# LineFollower2.net
KiCad netlist of a schematic drawn in Altium Designer
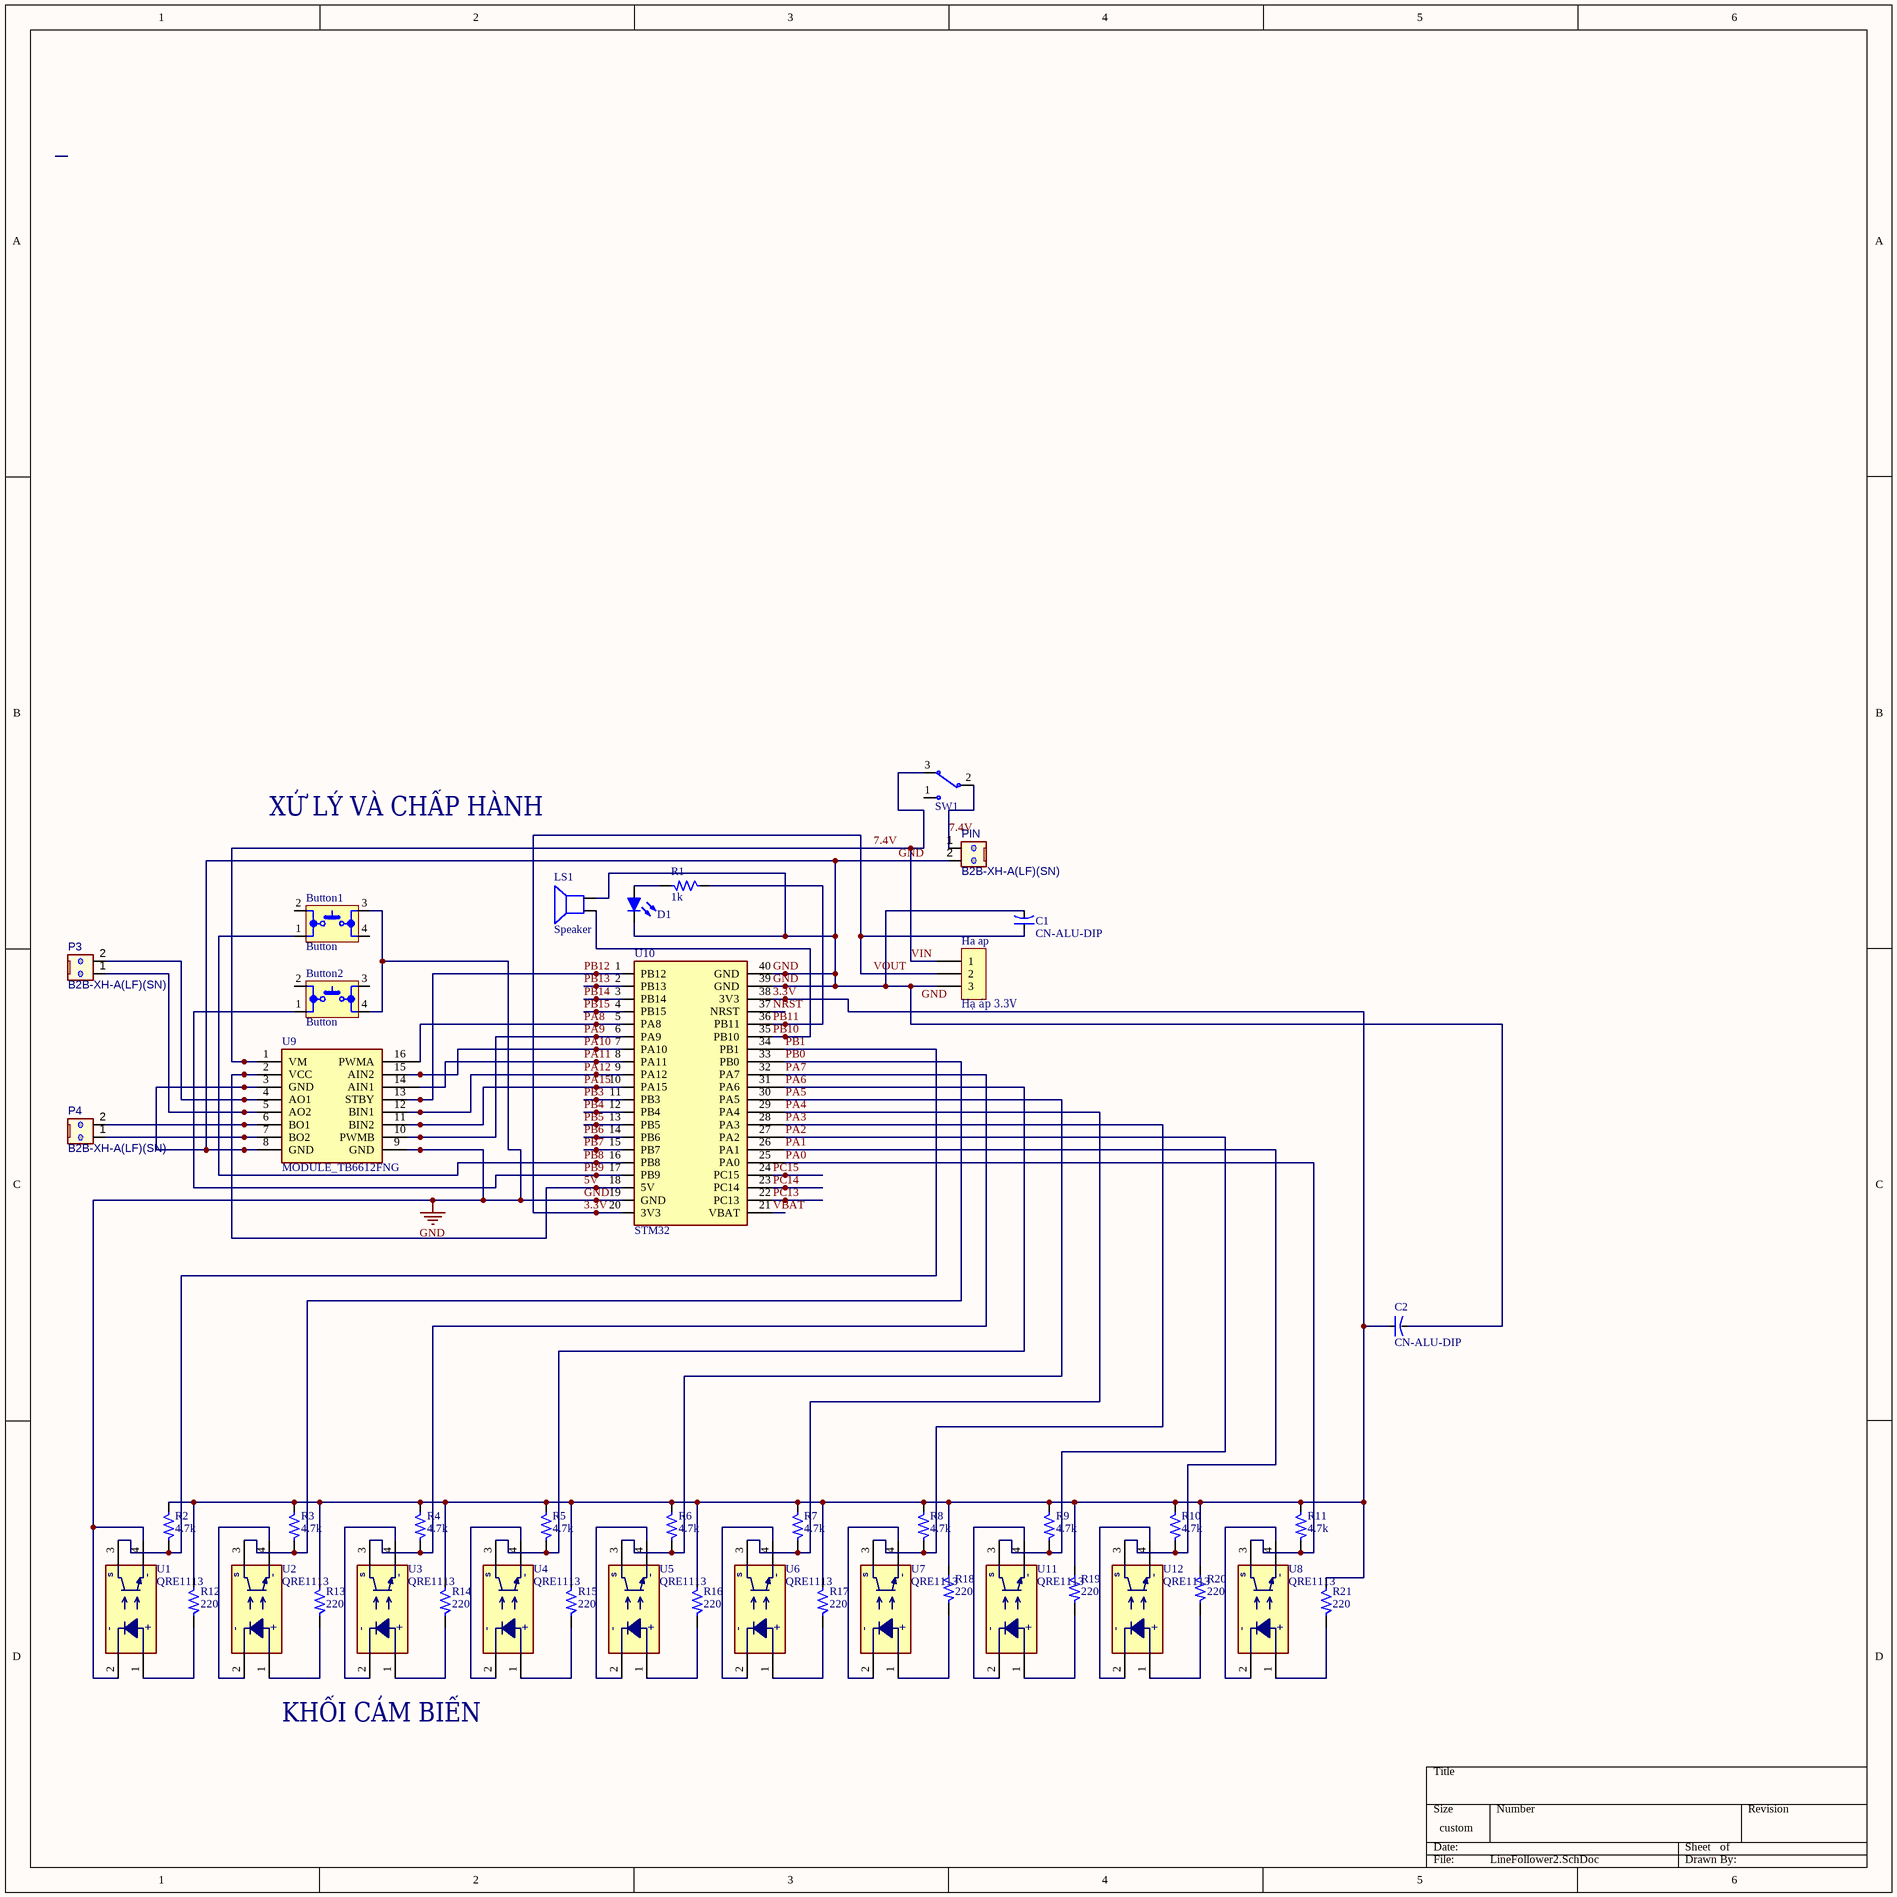
[diagram p0: LineFollower2.SchDoc]

(export (version "E")
  (design (tool "Eeschema 10.0.6"))
  (components
    (comp (ref "Button1")
      (value "Button")
      (footprint "1825910-6_BUTTON")
      (description "SWITCH TACTILE SPST-NO 0.05A 24V")
      (fields
        (field (name "MANUFACTURER") "TE Connectivity Alcoswitch")
        (field (name "MANUFACTURER PART NUMBER") "1825910-6")
      )
      (libsource (lib "Tactile Switch") (part "1825910-6"))
    )
    (comp (ref "Button2")
      (value "Button")
      (footprint "1825910-6_BUTTON")
      (description "SWITCH TACTILE SPST-NO 0.05A 24V")
      (fields
        (field (name "MANUFACTURER") "TE Connectivity Alcoswitch")
        (field (name "MANUFACTURER PART NUMBER") "1825910-6")
      )
      (libsource (lib "Tactile Switch") (part "1825910-6"))
    )
    (comp (ref "C1")
      (value "CN-ALU-DIP")
      (footprint "CA-ALU-2.54")
      (description "Capacitor (Semiconductor SIM Model)")
      (fields (field (name "PUBLISHER") "Altium Limited"))
      (libsource (lib "LIBRARY") (part "CN-ALU-DIP"))
    )
    (comp (ref "C2")
      (value "CN-ALU-DIP")
      (footprint "CA-ALU-2.54")
      (description "Capacitor (Semiconductor SIM Model)")
      (fields (field (name "PUBLISHER") "Altium Limited"))
      (libsource (lib "LIBRARY") (part "CN-ALU-DIP"))
    )
    (comp (ref "D1")
      (value "Led")
      (footprint "LED 5MM - RED")
      (description "Typical LED")
      (libsource (lib "led") (part "Led"))
    )
    (comp (ref "Ha ap")
      (value "Hạ áp 3.3V")
      (footprint "CON3")
      (description "Connector")
      (libsource (lib "Cty1") (part "CON3"))
    )
    (comp (ref "LS1")
      (value "Speaker")
      (footprint "SPEAKER")
      (description "Loudspeaker")
      (fields (field (name "PUBLISHER") "Altium Limited"))
      (libsource (lib "LIBRARY") (part "Speaker"))
    )
    (comp (ref "P3")
      (value "B2B-XH-A(LF)(SN)")
      (footprint "JST-B2B-XH-A_V")
      (description "CONN HEADER VERT 2POS 2.5MM")
      (libsource (lib "3. Connectors") (part "HEADER_2P_2.5MM"))
    )
    (comp (ref "P4")
      (value "B2B-XH-A(LF)(SN)")
      (footprint "JST-B2B-XH-A_V")
      (description "CONN HEADER VERT 2POS 2.5MM")
      (libsource (lib "3. Connectors") (part "HEADER_2P_2.5MM"))
    )
    (comp (ref "PIN")
      (value "B2B-XH-A(LF)(SN)")
      (footprint "JST-B2B-XH-A_V")
      (description "CONN HEADER VERT 2POS 2.5MM")
      (libsource (lib "") (part "HEADER_2P_2.5MM_1"))
    )
    (comp (ref "R1")
      (value "1k")
      (footprint "R1/4W")
      (description "Resistor 1/4W")
      (libsource (lib "Cty1") (part "Res"))
    )
    (comp (ref "R2")
      (value "4.7k")
      (footprint "R1/4W")
      (description "Resistor 1/4W")
      (libsource (lib "Cty1") (part "Res"))
    )
    (comp (ref "R3")
      (value "4.7k")
      (footprint "R1/4W")
      (description "Resistor 1/4W")
      (libsource (lib "Cty1") (part "Res"))
    )
    (comp (ref "R4")
      (value "4.7k")
      (footprint "R1/4W")
      (description "Resistor 1/4W")
      (libsource (lib "Cty1") (part "Res"))
    )
    (comp (ref "R5")
      (value "4.7k")
      (footprint "R1/4W")
      (description "Resistor 1/4W")
      (libsource (lib "Cty1") (part "Res"))
    )
    (comp (ref "R6")
      (value "4.7k")
      (footprint "R1/4W")
      (description "Resistor 1/4W")
      (libsource (lib "Cty1") (part "Res"))
    )
    (comp (ref "R7")
      (value "4.7k")
      (footprint "R1/4W")
      (description "Resistor 1/4W")
      (libsource (lib "Cty1") (part "Res"))
    )
    (comp (ref "R8")
      (value "4.7k")
      (footprint "R1/4W")
      (description "Resistor 1/4W")
      (libsource (lib "Cty1") (part "Res"))
    )
    (comp (ref "R9")
      (value "4.7k")
      (footprint "R1/4W")
      (description "Resistor 1/4W")
      (libsource (lib "Cty1") (part "Res"))
    )
    (comp (ref "R10")
      (value "4.7k")
      (footprint "R1/4W")
      (description "Resistor 1/4W")
      (libsource (lib "Cty1") (part "Res"))
    )
    (comp (ref "R11")
      (value "4.7k")
      (footprint "R1/4W")
      (description "Resistor 1/4W")
      (libsource (lib "Cty1") (part "Res"))
    )
    (comp (ref "R12")
      (value "220")
      (footprint "R1/4W")
      (description "Resistor 1/4W")
      (libsource (lib "Cty1") (part "Res"))
    )
    (comp (ref "R13")
      (value "220")
      (footprint "R1/4W")
      (description "Resistor 1/4W")
      (libsource (lib "Cty1") (part "Res"))
    )
    (comp (ref "R14")
      (value "220")
      (footprint "R1/4W")
      (description "Resistor 1/4W")
      (libsource (lib "Cty1") (part "Res"))
    )
    (comp (ref "R15")
      (value "220")
      (footprint "R1/4W")
      (description "Resistor 1/4W")
      (libsource (lib "Cty1") (part "Res"))
    )
    (comp (ref "R16")
      (value "220")
      (footprint "R1/4W")
      (description "Resistor 1/4W")
      (libsource (lib "Cty1") (part "Res"))
    )
    (comp (ref "R17")
      (value "220")
      (footprint "R1/4W")
      (description "Resistor 1/4W")
      (libsource (lib "Cty1") (part "Res"))
    )
    (comp (ref "R18")
      (value "220")
      (footprint "R1/4W")
      (description "Resistor 1/4W")
      (libsource (lib "Cty1") (part "Res"))
    )
    (comp (ref "R19")
      (value "220")
      (footprint "R1/4W")
      (description "Resistor 1/4W")
      (libsource (lib "Cty1") (part "Res"))
    )
    (comp (ref "R20")
      (value "220")
      (footprint "R1/4W")
      (description "Resistor 1/4W")
      (libsource (lib "Cty1") (part "Res"))
    )
    (comp (ref "R21")
      (value "220")
      (footprint "R1/4W")
      (description "Resistor 1/4W")
      (libsource (lib "Cty1") (part "Res"))
    )
    (comp (ref "SW1")
      (value "EG1218")
      (footprint "EG1218")
      (description "SWITCH SLIDE SPDT 200MA 30V")
      (fields (field (name "MANUFACTURER") "E-Switch"))
      (libsource (lib "3. Connectors") (part "SW_SPDT"))
    )
    (comp (ref "U1")
      (value "QRE1113")
      (footprint "QRE1113")
      (description "REFLECTIVE OPTICAL SENSOR SMD")
      (libsource (lib "Sensors") (part "QRE1113"))
    )
    (comp (ref "U2")
      (value "QRE1113")
      (footprint "QRE1113")
      (description "REFLECTIVE OPTICAL SENSOR SMD")
      (libsource (lib "Sensors") (part "QRE1113"))
    )
    (comp (ref "U3")
      (value "QRE1113")
      (footprint "QRE1113")
      (description "REFLECTIVE OPTICAL SENSOR SMD")
      (libsource (lib "Sensors") (part "QRE1113"))
    )
    (comp (ref "U4")
      (value "QRE1113")
      (footprint "QRE1113")
      (description "REFLECTIVE OPTICAL SENSOR SMD")
      (libsource (lib "Sensors") (part "QRE1113"))
    )
    (comp (ref "U5")
      (value "QRE1113")
      (footprint "QRE1113")
      (description "REFLECTIVE OPTICAL SENSOR SMD")
      (libsource (lib "Sensors") (part "QRE1113"))
    )
    (comp (ref "U6")
      (value "QRE1113")
      (footprint "QRE1113")
      (description "REFLECTIVE OPTICAL SENSOR SMD")
      (libsource (lib "Sensors") (part "QRE1113"))
    )
    (comp (ref "U7")
      (value "QRE1113")
      (footprint "QRE1113")
      (description "REFLECTIVE OPTICAL SENSOR SMD")
      (libsource (lib "Sensors") (part "QRE1113"))
    )
    (comp (ref "U8")
      (value "QRE1113")
      (footprint "QRE1113")
      (description "REFLECTIVE OPTICAL SENSOR SMD")
      (libsource (lib "Sensors") (part "QRE1113"))
    )
    (comp (ref "U9")
      (value "MODULE_TB6612FNG")
      (footprint "MODULE_TB6612FNG")
      (description "Module Dual Motor Driver 2.5-13.5V 3.2A Peak 21x18mm")
      (libsource (lib "Motor Drivers") (part "MODULE_TB6612FNG"))
    )
    (comp (ref "U10")
      (value "STM32")
      (footprint "STM32")
      (libsource (lib "Other Microcontrollers") (part "STM32"))
    )
    (comp (ref "U11")
      (value "QRE1113")
      (footprint "QRE1113")
      (description "REFLECTIVE OPTICAL SENSOR SMD")
      (libsource (lib "Sensors") (part "QRE1113"))
    )
    (comp (ref "U12")
      (value "QRE1113")
      (footprint "QRE1113")
      (description "REFLECTIVE OPTICAL SENSOR SMD")
      (libsource (lib "Sensors") (part "QRE1113"))
    )
  )
  (nets
    (net (code "1") (name "/3.3V") (class "Default")
      (node (ref "C1") (pin "1") (pinfunction "1_1") (pintype "passive"))
      (node (ref "C2") (pin "1") (pinfunction "1_1") (pintype "passive"))
      (node (ref "Ha ap") (pin "2") (pinfunction "2_2") (pintype "passive"))
      (node (ref "R10") (pin "1") (pinfunction "1_1") (pintype "passive"))
      (node (ref "R11") (pin "1") (pinfunction "1_1") (pintype "passive"))
      (node (ref "R12") (pin "1") (pinfunction "1_1") (pintype "passive"))
      (node (ref "R13") (pin "1") (pinfunction "1_1") (pintype "passive"))
      (node (ref "R14") (pin "1") (pinfunction "1_1") (pintype "passive"))
      (node (ref "R15") (pin "1") (pinfunction "1_1") (pintype "passive"))
      (node (ref "R16") (pin "1") (pinfunction "1_1") (pintype "passive"))
      (node (ref "R17") (pin "1") (pinfunction "1_1") (pintype "passive"))
      (node (ref "R18") (pin "1") (pinfunction "1_1") (pintype "passive"))
      (node (ref "R19") (pin "1") (pinfunction "1_1") (pintype "passive"))
      (node (ref "R2") (pin "1") (pinfunction "1_1") (pintype "passive"))
      (node (ref "R20") (pin "1") (pinfunction "1_1") (pintype "passive"))
      (node (ref "R21") (pin "1") (pinfunction "1_1") (pintype "passive"))
      (node (ref "R3") (pin "1") (pinfunction "1_1") (pintype "passive"))
      (node (ref "R4") (pin "1") (pinfunction "1_1") (pintype "passive"))
      (node (ref "R5") (pin "1") (pinfunction "1_1") (pintype "passive"))
      (node (ref "R6") (pin "1") (pinfunction "1_1") (pintype "passive"))
      (node (ref "R7") (pin "1") (pinfunction "1_1") (pintype "passive"))
      (node (ref "R8") (pin "1") (pinfunction "1_1") (pintype "passive"))
      (node (ref "R9") (pin "1") (pinfunction "1_1") (pintype "passive"))
      (node (ref "U10") (pin "20") (pinfunction "3V3_20") (pintype "passive"))
      (node (ref "U10") (pin "38") (pinfunction "3V3_38") (pintype "passive"))
    )
    (net (code "2") (name "/5V") (class "Default")
      (node (ref "U10") (pin "18") (pinfunction "5V_18") (pintype "passive"))
      (node (ref "U9") (pin "2") (pinfunction "VCC_2") (pintype "passive"))
    )
    (net (code "3") (name "/7.4V") (class "Default")
      (node (ref "Ha ap") (pin "1") (pinfunction "1_1") (pintype "passive"))
      (node (ref "PIN") (pin "1") (pinfunction "1_1") (pintype "passive"))
      (node (ref "SW1") (pin "2") (pinfunction "2_2") (pintype "passive"))
      (node (ref "SW1") (pin "3") (pinfunction "3_3") (pintype "passive"))
      (node (ref "U9") (pin "1") (pinfunction "VM_1") (pintype "passive"))
    )
    (net (code "4") (name "/NRST") (class "Default")
      (node (ref "U10") (pin "37") (pinfunction "NRST_37") (pintype "passive"))
    )
    (net (code "5") (name "/PA0") (class "Default")
      (node (ref "R11") (pin "2") (pinfunction "2_2") (pintype "passive"))
      (node (ref "U10") (pin "25") (pinfunction "PA0_25") (pintype "passive"))
      (node (ref "U8") (pin "3") (pinfunction "SIGNAL_3") (pintype "passive"))
    )
    (net (code "6") (name "/PA1") (class "Default")
      (node (ref "R10") (pin "2") (pinfunction "2_2") (pintype "passive"))
      (node (ref "U10") (pin "26") (pinfunction "PA1_26") (pintype "passive"))
      (node (ref "U12") (pin "3") (pinfunction "SIGNAL_3") (pintype "passive"))
    )
    (net (code "7") (name "/PA2") (class "Default")
      (node (ref "R9") (pin "2") (pinfunction "2_2") (pintype "passive"))
      (node (ref "U10") (pin "27") (pinfunction "PA2_27") (pintype "passive"))
      (node (ref "U11") (pin "3") (pinfunction "SIGNAL_3") (pintype "passive"))
    )
    (net (code "8") (name "/PA3") (class "Default")
      (node (ref "R8") (pin "2") (pinfunction "2_2") (pintype "passive"))
      (node (ref "U10") (pin "28") (pinfunction "PA3_28") (pintype "passive"))
      (node (ref "U7") (pin "3") (pinfunction "SIGNAL_3") (pintype "passive"))
    )
    (net (code "9") (name "/PA4") (class "Default")
      (node (ref "R7") (pin "2") (pinfunction "2_2") (pintype "passive"))
      (node (ref "U10") (pin "29") (pinfunction "PA4_29") (pintype "passive"))
      (node (ref "U6") (pin "3") (pinfunction "SIGNAL_3") (pintype "passive"))
    )
    (net (code "10") (name "/PA5") (class "Default")
      (node (ref "R6") (pin "2") (pinfunction "2_2") (pintype "passive"))
      (node (ref "U10") (pin "30") (pinfunction "PA5_30") (pintype "passive"))
      (node (ref "U5") (pin "3") (pinfunction "SIGNAL_3") (pintype "passive"))
    )
    (net (code "11") (name "/PA6") (class "Default")
      (node (ref "R5") (pin "2") (pinfunction "2_2") (pintype "passive"))
      (node (ref "U10") (pin "31") (pinfunction "PA6_31") (pintype "passive"))
      (node (ref "U4") (pin "3") (pinfunction "SIGNAL_3") (pintype "passive"))
    )
    (net (code "12") (name "/PA7") (class "Default")
      (node (ref "R4") (pin "2") (pinfunction "2_2") (pintype "passive"))
      (node (ref "U10") (pin "32") (pinfunction "PA7_32") (pintype "passive"))
      (node (ref "U3") (pin "3") (pinfunction "SIGNAL_3") (pintype "passive"))
    )
    (net (code "13") (name "/PA8") (class "Default")
      (node (ref "U10") (pin "5") (pinfunction "PA8_5") (pintype "passive"))
      (node (ref "U9") (pin "16") (pinfunction "PWMA_16") (pintype "passive"))
    )
    (net (code "14") (name "/PA9") (class "Default")
      (node (ref "U10") (pin "6") (pinfunction "PA9_6") (pintype "passive"))
      (node (ref "U9") (pin "10") (pinfunction "PWMB_10") (pintype "passive"))
    )
    (net (code "15") (name "/PA10") (class "Default")
      (node (ref "U10") (pin "7") (pinfunction "PA10_7") (pintype "passive"))
      (node (ref "U9") (pin "15") (pinfunction "AIN2_15") (pintype "passive"))
    )
    (net (code "16") (name "/PA11") (class "Default")
      (node (ref "U10") (pin "8") (pinfunction "PA11_8") (pintype "passive"))
      (node (ref "U9") (pin "14") (pinfunction "AIN1_14") (pintype "passive"))
    )
    (net (code "17") (name "/PA12") (class "Default")
      (node (ref "U10") (pin "9") (pinfunction "PA12_9") (pintype "passive"))
      (node (ref "U9") (pin "12") (pinfunction "BIN1_12") (pintype "passive"))
    )
    (net (code "18") (name "/PA15") (class "Default")
      (node (ref "U10") (pin "10") (pinfunction "PA15_10") (pintype "passive"))
      (node (ref "U9") (pin "11") (pinfunction "BIN2_11") (pintype "passive"))
    )
    (net (code "19") (name "/PB0") (class "Default")
      (node (ref "R3") (pin "2") (pinfunction "2_2") (pintype "passive"))
      (node (ref "U10") (pin "33") (pinfunction "PB0_33") (pintype "passive"))
      (node (ref "U2") (pin "3") (pinfunction "SIGNAL_3") (pintype "passive"))
    )
    (net (code "20") (name "/PB1") (class "Default")
      (node (ref "R2") (pin "2") (pinfunction "2_2") (pintype "passive"))
      (node (ref "U1") (pin "3") (pinfunction "SIGNAL_3") (pintype "passive"))
      (node (ref "U10") (pin "34") (pinfunction "PB1_34") (pintype "passive"))
    )
    (net (code "21") (name "/PB3") (class "Default")
      (node (ref "U10") (pin "11") (pinfunction "PB3_11") (pintype "passive"))
    )
    (net (code "22") (name "/PB4") (class "Default")
      (node (ref "U10") (pin "12") (pinfunction "PB4_12") (pintype "passive"))
    )
    (net (code "23") (name "/PB5") (class "Default")
      (node (ref "U10") (pin "13") (pinfunction "PB5_13") (pintype "passive"))
    )
    (net (code "24") (name "/PB6") (class "Default")
      (node (ref "U10") (pin "14") (pinfunction "PB6_14") (pintype "passive"))
    )
    (net (code "25") (name "/PB7") (class "Default")
      (node (ref "U10") (pin "15") (pinfunction "PB7_15") (pintype "passive"))
    )
    (net (code "26") (name "/PB8") (class "Default")
      (node (ref "Button1") (pin "1") (pinfunction "1_1") (pintype "passive"))
      (node (ref "U10") (pin "16") (pinfunction "PB8_16") (pintype "passive"))
    )
    (net (code "27") (name "/PB9") (class "Default")
      (node (ref "Button2") (pin "1") (pinfunction "1_1") (pintype "passive"))
      (node (ref "U10") (pin "17") (pinfunction "PB9_17") (pintype "passive"))
    )
    (net (code "28") (name "/PB10") (class "Default")
      (node (ref "LS1") (pin "1") (pinfunction "1_1") (pintype "passive"))
      (node (ref "U10") (pin "35") (pinfunction "PB10_35") (pintype "passive"))
    )
    (net (code "29") (name "/PB11") (class "Default")
      (node (ref "R1") (pin "1") (pinfunction "1_1") (pintype "passive"))
      (node (ref "U10") (pin "36") (pinfunction "PB11_36") (pintype "passive"))
    )
    (net (code "30") (name "/PB12") (class "Default")
      (node (ref "U10") (pin "1") (pinfunction "PB12_1") (pintype "passive"))
      (node (ref "U9") (pin "13") (pinfunction "STBY_13") (pintype "passive"))
    )
    (net (code "31") (name "/PB13") (class "Default")
      (node (ref "U10") (pin "2") (pinfunction "PB13_2") (pintype "passive"))
    )
    (net (code "32") (name "/PB14") (class "Default")
      (node (ref "U10") (pin "3") (pinfunction "PB14_3") (pintype "passive"))
    )
    (net (code "33") (name "/PB15") (class "Default")
      (node (ref "U10") (pin "4") (pinfunction "PB15_4") (pintype "passive"))
    )
    (net (code "34") (name "/PC13") (class "Default")
      (node (ref "U10") (pin "22") (pinfunction "PC13_22") (pintype "passive"))
    )
    (net (code "35") (name "/PC14") (class "Default")
      (node (ref "U10") (pin "23") (pinfunction "PC14_23") (pintype "passive"))
    )
    (net (code "36") (name "/PC15") (class "Default")
      (node (ref "U10") (pin "24") (pinfunction "PC15_24") (pintype "passive"))
    )
    (net (code "37") (name "/VBAT") (class "Default")
      (node (ref "U10") (pin "21") (pinfunction "VBAT_21") (pintype "passive"))
    )
    (net (code "38") (name "GND") (class "Default")
      (node (ref "Button1") (pin "3") (pinfunction "3_3") (pintype "passive"))
      (node (ref "Button2") (pin "4") (pinfunction "4_4") (pintype "passive"))
      (node (ref "C1") (pin "2") (pinfunction "2_2") (pintype "passive"))
      (node (ref "C2") (pin "2") (pinfunction "2_2") (pintype "passive"))
      (node (ref "D1") (pin "2") (pinfunction "K_2") (pintype "passive"))
      (node (ref "Ha ap") (pin "3") (pinfunction "3_3") (pintype "passive"))
      (node (ref "LS1") (pin "2") (pinfunction "2_2") (pintype "passive"))
      (node (ref "PIN") (pin "2") (pinfunction "2_2") (pintype "passive"))
      (node (ref "U1") (pin "2") (pinfunction "GND_2") (pintype "passive"))
      (node (ref "U1") (pin "4") (pinfunction "GND_4") (pintype "passive"))
      (node (ref "U10") (pin "19") (pinfunction "GND_19") (pintype "passive"))
      (node (ref "U10") (pin "39") (pinfunction "GND_39") (pintype "passive"))
      (node (ref "U10") (pin "40") (pinfunction "GND_40") (pintype "passive"))
      (node (ref "U9") (pin "3") (pinfunction "GND_3") (pintype "passive"))
      (node (ref "U9") (pin "8") (pinfunction "GND_8") (pintype "passive"))
      (node (ref "U9") (pin "9") (pinfunction "GND_9") (pintype "passive"))
    )
    (net (code "39") (name "Net-(D1-A)") (class "Default")
      (node (ref "D1") (pin "1") (pinfunction "A_1") (pintype "passive"))
      (node (ref "R1") (pin "2") (pinfunction "2_2") (pintype "passive"))
    )
    (net (code "40") (name "Net-(U1-VCC)") (class "Default")
      (node (ref "R12") (pin "2") (pinfunction "2_2") (pintype "passive"))
      (node (ref "U1") (pin "1") (pinfunction "VCC_1") (pintype "passive"))
    )
    (net (code "41") (name "Net-(U2-GND-Pad2)") (class "Default")
      (node (ref "U2") (pin "2") (pinfunction "GND_2") (pintype "passive"))
      (node (ref "U2") (pin "4") (pinfunction "GND_4") (pintype "passive"))
    )
    (net (code "42") (name "Net-(U2-VCC)") (class "Default")
      (node (ref "R13") (pin "2") (pinfunction "2_2") (pintype "passive"))
      (node (ref "U2") (pin "1") (pinfunction "VCC_1") (pintype "passive"))
    )
    (net (code "43") (name "Net-(U3-GND-Pad2)") (class "Default")
      (node (ref "U3") (pin "2") (pinfunction "GND_2") (pintype "passive"))
      (node (ref "U3") (pin "4") (pinfunction "GND_4") (pintype "passive"))
    )
    (net (code "44") (name "Net-(U3-VCC)") (class "Default")
      (node (ref "R14") (pin "2") (pinfunction "2_2") (pintype "passive"))
      (node (ref "U3") (pin "1") (pinfunction "VCC_1") (pintype "passive"))
    )
    (net (code "45") (name "Net-(U4-GND-Pad2)") (class "Default")
      (node (ref "U4") (pin "2") (pinfunction "GND_2") (pintype "passive"))
      (node (ref "U4") (pin "4") (pinfunction "GND_4") (pintype "passive"))
    )
    (net (code "46") (name "Net-(U4-VCC)") (class "Default")
      (node (ref "R15") (pin "2") (pinfunction "2_2") (pintype "passive"))
      (node (ref "U4") (pin "1") (pinfunction "VCC_1") (pintype "passive"))
    )
    (net (code "47") (name "Net-(U5-GND-Pad2)") (class "Default")
      (node (ref "U5") (pin "2") (pinfunction "GND_2") (pintype "passive"))
      (node (ref "U5") (pin "4") (pinfunction "GND_4") (pintype "passive"))
    )
    (net (code "48") (name "Net-(U5-VCC)") (class "Default")
      (node (ref "R16") (pin "2") (pinfunction "2_2") (pintype "passive"))
      (node (ref "U5") (pin "1") (pinfunction "VCC_1") (pintype "passive"))
    )
    (net (code "49") (name "Net-(U6-GND-Pad2)") (class "Default")
      (node (ref "U6") (pin "2") (pinfunction "GND_2") (pintype "passive"))
      (node (ref "U6") (pin "4") (pinfunction "GND_4") (pintype "passive"))
    )
    (net (code "50") (name "Net-(U6-VCC)") (class "Default")
      (node (ref "R17") (pin "2") (pinfunction "2_2") (pintype "passive"))
      (node (ref "U6") (pin "1") (pinfunction "VCC_1") (pintype "passive"))
    )
    (net (code "51") (name "Net-(U7-GND-Pad2)") (class "Default")
      (node (ref "U7") (pin "2") (pinfunction "GND_2") (pintype "passive"))
      (node (ref "U7") (pin "4") (pinfunction "GND_4") (pintype "passive"))
    )
    (net (code "52") (name "Net-(U7-VCC)") (class "Default")
      (node (ref "R18") (pin "2") (pinfunction "2_2") (pintype "passive"))
      (node (ref "U7") (pin "1") (pinfunction "VCC_1") (pintype "passive"))
    )
    (net (code "53") (name "Net-(U8-GND-Pad2)") (class "Default")
      (node (ref "U8") (pin "2") (pinfunction "GND_2") (pintype "passive"))
      (node (ref "U8") (pin "4") (pinfunction "GND_4") (pintype "passive"))
    )
    (net (code "54") (name "Net-(U8-VCC)") (class "Default")
      (node (ref "R21") (pin "2") (pinfunction "2_2") (pintype "passive"))
      (node (ref "U8") (pin "1") (pinfunction "VCC_1") (pintype "passive"))
    )
    (net (code "55") (name "Net-(U9-AO1)") (class "Default")
      (node (ref "P3") (pin "2") (pinfunction "2_2") (pintype "passive"))
      (node (ref "U9") (pin "4") (pinfunction "AO1_4") (pintype "passive"))
    )
    (net (code "56") (name "Net-(U9-AO2)") (class "Default")
      (node (ref "P3") (pin "1") (pinfunction "1_1") (pintype "passive"))
      (node (ref "U9") (pin "5") (pinfunction "AO2_5") (pintype "passive"))
    )
    (net (code "57") (name "Net-(U9-BO1)") (class "Default")
      (node (ref "P4") (pin "2") (pinfunction "2_2") (pintype "passive"))
      (node (ref "U9") (pin "6") (pinfunction "BO1_6") (pintype "passive"))
    )
    (net (code "58") (name "Net-(U9-BO2)") (class "Default")
      (node (ref "P4") (pin "1") (pinfunction "1_1") (pintype "passive"))
      (node (ref "U9") (pin "7") (pinfunction "BO2_7") (pintype "passive"))
    )
    (net (code "59") (name "Net-(U11-GND-Pad2)") (class "Default")
      (node (ref "U11") (pin "2") (pinfunction "GND_2") (pintype "passive"))
      (node (ref "U11") (pin "4") (pinfunction "GND_4") (pintype "passive"))
    )
    (net (code "60") (name "Net-(U11-VCC)") (class "Default")
      (node (ref "R19") (pin "2") (pinfunction "2_2") (pintype "passive"))
      (node (ref "U11") (pin "1") (pinfunction "VCC_1") (pintype "passive"))
    )
    (net (code "61") (name "Net-(U12-GND-Pad2)") (class "Default")
      (node (ref "U12") (pin "2") (pinfunction "GND_2") (pintype "passive"))
      (node (ref "U12") (pin "4") (pinfunction "GND_4") (pintype "passive"))
    )
    (net (code "62") (name "Net-(U12-VCC)") (class "Default")
      (node (ref "R20") (pin "2") (pinfunction "2_2") (pintype "passive"))
      (node (ref "U12") (pin "1") (pinfunction "VCC_1") (pintype "passive"))
    )
    (net (code "63") (name "unconnected-(Button1-Pad2)") (class "Default")
      (node (ref "Button1") (pin "2") (pinfunction "2_2") (pintype "passive"))
    )
    (net (code "64") (name "unconnected-(Button1-Pad4)") (class "Default")
      (node (ref "Button1") (pin "4") (pinfunction "4_4") (pintype "passive"))
    )
    (net (code "65") (name "unconnected-(Button2-Pad2)") (class "Default")
      (node (ref "Button2") (pin "2") (pinfunction "2_2") (pintype "passive"))
    )
    (net (code "66") (name "unconnected-(Button2-Pad3)") (class "Default")
      (node (ref "Button2") (pin "3") (pinfunction "3_3") (pintype "passive"))
    )
    (net (code "67") (name "unconnected-(SW1-Pad1)") (class "Default")
      (node (ref "SW1") (pin "1") (pinfunction "1_1") (pintype "passive"))
    )
  )
)
